# LAN.net
KiCad netlist of a schematic drawn in Altium Designer
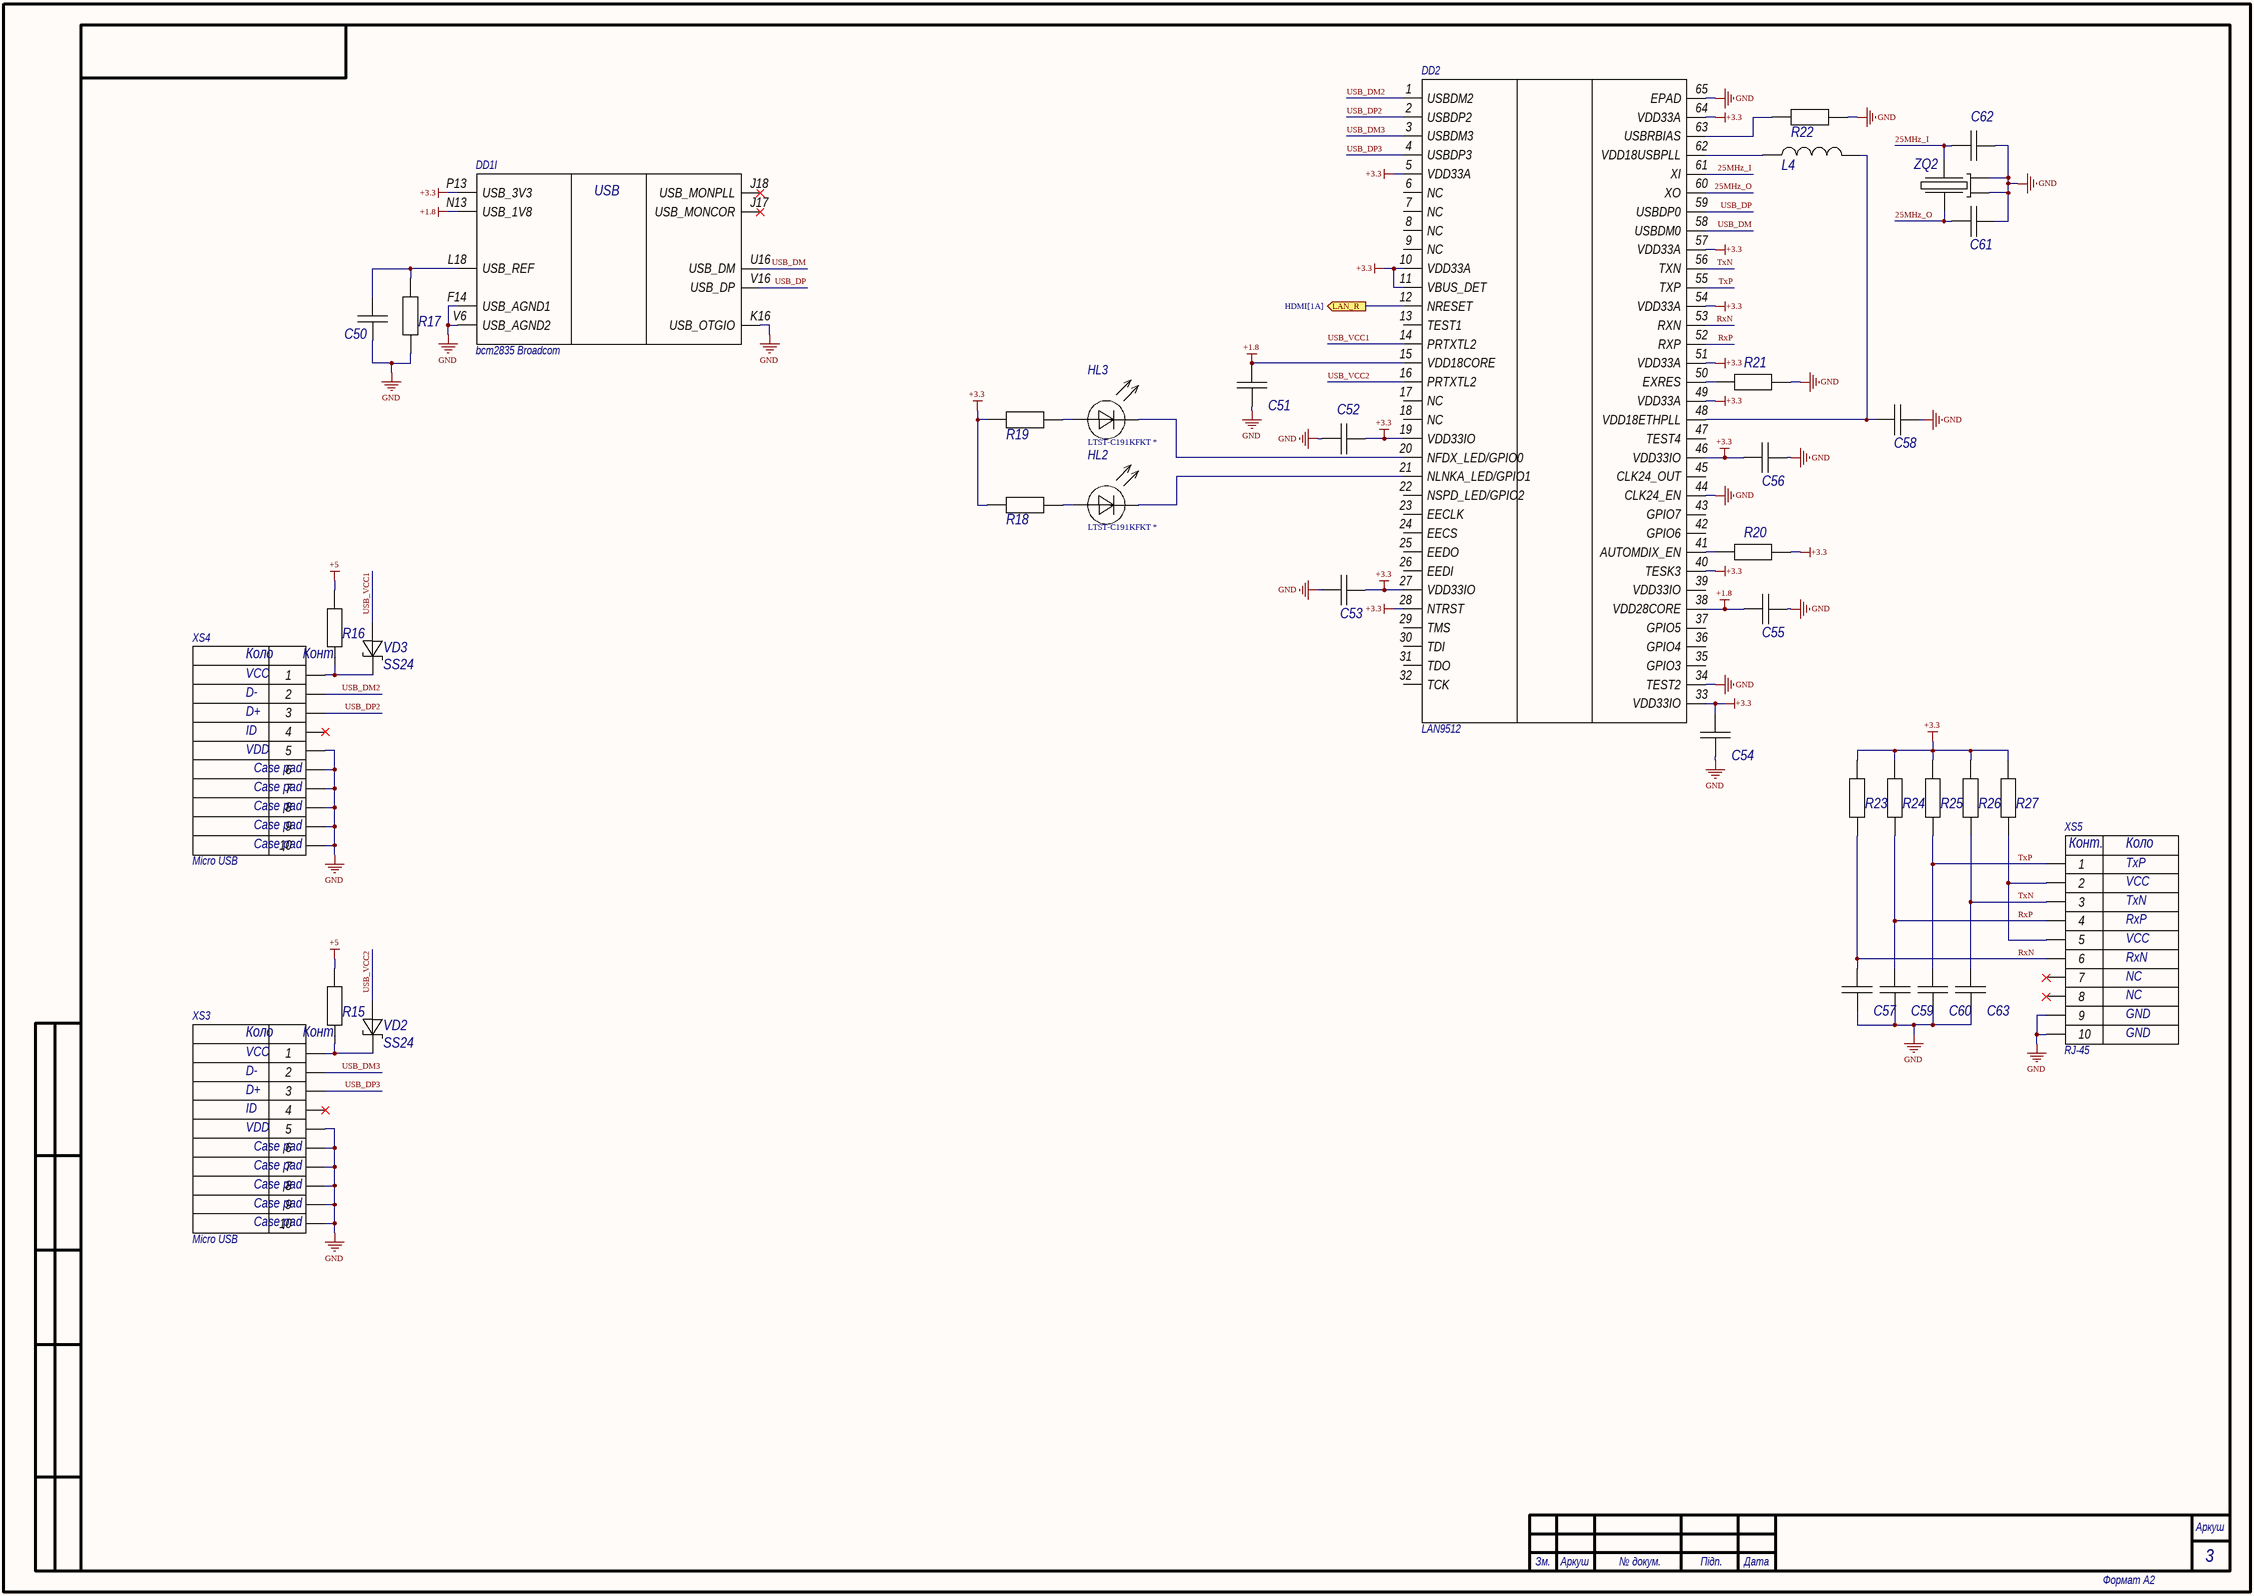
[diagram p0: LAN.SchDoc]

(export (version "E")
  (design (tool "Eeschema 10.0.6"))
  (components
    (comp (ref "C50")
      (value "C-0603 * * * * *")
      (footprint "С-0603")
      (description "Generic")
      (libsource (lib "Schlib1") (part "С-0603"))
    )
    (comp (ref "C51")
      (value "C-0402 * * * * *")
      (footprint "C-0402")
      (description "Generic")
      (libsource (lib "Schlib1") (part "С-0402"))
    )
    (comp (ref "C52")
      (value "C-0402 * * * * *")
      (footprint "C-0402")
      (description "Generic")
      (libsource (lib "Schlib1") (part "С-0402"))
    )
    (comp (ref "C53")
      (value "C-0402 * * * * *")
      (footprint "C-0402")
      (description "Generic")
      (libsource (lib "Schlib1") (part "С-0402"))
    )
    (comp (ref "C54")
      (value "C-0402 * * * * *")
      (footprint "C-0402")
      (description "Generic")
      (libsource (lib "Schlib1") (part "С-0402"))
    )
    (comp (ref "C55")
      (value "C-0402 * * * * *")
      (footprint "C-0402")
      (description "Generic")
      (libsource (lib "Schlib1") (part "С-0402"))
    )
    (comp (ref "C56")
      (value "C-0402 * * * * *")
      (footprint "C-0402")
      (description "Generic")
      (libsource (lib "Schlib1") (part "С-0402"))
    )
    (comp (ref "C57")
      (value "C-0603 * * * * *")
      (footprint "С-0603")
      (description "Generic")
      (libsource (lib "Schlib1") (part "С-0603"))
    )
    (comp (ref "C58")
      (value "C-0402 * * * * *")
      (footprint "C-0402")
      (description "Generic")
      (libsource (lib "Schlib1") (part "С-0402"))
    )
    (comp (ref "C59")
      (value "C-0603 * * * * *")
      (footprint "С-0603")
      (description "Generic")
      (libsource (lib "Schlib1") (part "С-0603"))
    )
    (comp (ref "C60")
      (value "C-0603 * * * * *")
      (footprint "С-0603")
      (description "Generic")
      (libsource (lib "Schlib1") (part "С-0603"))
    )
    (comp (ref "C61")
      (value "C-0402 * * * * *")
      (footprint "C-0402")
      (description "Generic")
      (libsource (lib "Schlib1") (part "С-0402"))
    )
    (comp (ref "C62")
      (value "C-0402 * * * * *")
      (footprint "C-0402")
      (description "Generic")
      (libsource (lib "Schlib1") (part "С-0402"))
    )
    (comp (ref "C63")
      (value "C-0603 * * * * *")
      (footprint "С-0603")
      (description "Generic")
      (libsource (lib "Schlib1") (part "С-0603"))
    )
    (comp (ref "DD1")
      (value "bcm2835 Broadcom")
      (footprint "BGA81C65P18X18_1200X1200")
      (description "BCM2835 ARM-based processor")
      (fields (field (name "MANUFACTURER") "Broadcom"))
      (libsource (lib "Schlib1") (part "bcm2835"))
    )
    (comp (ref "DD2")
      (value "LAN9512")
      (footprint "QFN64_9x9MC_MCH")
      (description "Ethernet + USB Controller")
      (libsource (lib "Schlib1") (part "LAN9512"))
    )
    (comp (ref "HL2")
      (value "LTST-C191KFKT *")
      (footprint "LED_DIALIGHT_598_DIA")
      (description "Generic LED 0603")
      (libsource (lib "Schlib1") (part "LED 0603"))
    )
    (comp (ref "HL3")
      (value "LTST-C191KFKT *")
      (footprint "LED_DIALIGHT_598_DIA")
      (description "Generic LED 0603")
      (libsource (lib "Schlib1") (part "LED 0603"))
    )
    (comp (ref "L4")
      (value "R-0402 * * * *")
      (footprint "FB-0805")
      (description "Generic")
      (libsource (lib "Schlib1") (part "Ferrite Bead 0805"))
    )
    (comp (ref "R15")
      (value "R-0603 * * * *")
      (footprint "R-0603")
      (description "Generic")
      (libsource (lib "") (part "R-0603_1"))
    )
    (comp (ref "R16")
      (value "R-0603 * * * *")
      (footprint "R-0603")
      (description "Generic")
      (libsource (lib "") (part "R-0603_1"))
    )
    (comp (ref "R17")
      (value "R-0603 * * * *")
      (footprint "R-0603")
      (description "Generic")
      (libsource (lib "") (part "R-0603_1"))
    )
    (comp (ref "R18")
      (value "R-0603 * * * *")
      (footprint "R-0603")
      (description "Generic")
      (libsource (lib "Schlib1") (part "R-0603"))
    )
    (comp (ref "R19")
      (value "R-0603 * * * *")
      (footprint "R-0603")
      (description "Generic")
      (libsource (lib "Schlib1") (part "R-0603"))
    )
    (comp (ref "R20")
      (value "R-0402 * * * *")
      (footprint "R-0402")
      (description "Generic")
      (libsource (lib "Schlib1") (part "R-0402"))
    )
    (comp (ref "R21")
      (value "R-0402 * * * *")
      (footprint "R-0402")
      (description "Generic")
      (libsource (lib "Schlib1") (part "R-0402"))
    )
    (comp (ref "R22")
      (value "R-0402 * * * *")
      (footprint "R-0402")
      (description "Generic")
      (libsource (lib "Schlib1") (part "R-0402"))
    )
    (comp (ref "R23")
      (value "R-0603 * * * *")
      (footprint "R-0603")
      (description "Generic")
      (libsource (lib "") (part "R-0603_2"))
    )
    (comp (ref "R24")
      (value "R-0603 * * * *")
      (footprint "R-0603")
      (description "Generic")
      (libsource (lib "") (part "R-0603_2"))
    )
    (comp (ref "R25")
      (value "R-0603 * * * *")
      (footprint "R-0603")
      (description "Generic")
      (libsource (lib "") (part "R-0603_2"))
    )
    (comp (ref "R26")
      (value "R-0603 * * * *")
      (footprint "R-0603")
      (description "Generic")
      (libsource (lib "") (part "R-0603_2"))
    )
    (comp (ref "R27")
      (value "R-0603 * * * *")
      (footprint "R-0603")
      (description "Generic")
      (libsource (lib "") (part "R-0603_2"))
    )
    (comp (ref "VD2")
      (value "SS24 *")
      (footprint "SS14")
      (description "SS24 Shotky")
      (fields (field (name "NAME") "SS24"))
      (libsource (lib "Schlib1") (part "SS24"))
    )
    (comp (ref "VD3")
      (value "SS24 *")
      (footprint "SS14")
      (description "SS24 Shotky")
      (fields (field (name "NAME") "SS24"))
      (libsource (lib "Schlib1") (part "SS24"))
    )
    (comp (ref "XS3")
      (value "Micro USB")
      (footprint "micro-usb")
      (description "Micro-USB connector for SMT mounting")
      (libsource (lib "Schlib1") (part "Micro-USB"))
    )
    (comp (ref "XS4")
      (value "Micro USB")
      (footprint "micro-usb")
      (description "Micro-USB connector for SMT mounting")
      (libsource (lib "Schlib1") (part "Micro-USB"))
    )
    (comp (ref "XS5")
      (value "RJ-45")
      (footprint "CONN8_2041126-1_TEC")
      (description "RJ-45 connector SMT mounting")
      (libsource (lib "Schlib1") (part "RJ-45"))
    )
    (comp (ref "ZQ2")
      (value "TXC19.2 *")
      (footprint "CRYSTAL_TXC_7B")
      (description "TXC19.2 crystal 19.2 MHz")
      (libsource (lib "Schlib1") (part "TXC19.2"))
    )
  )
  (nets
    (net (code "1") (name "+1.8") (class "Default")
      (node (ref "C51") (pin "2") (pinfunction "2_2") (pintype "passive"))
      (node (ref "C55") (pin "2") (pinfunction "2_2") (pintype "passive"))
      (node (ref "DD1") (pin "N13") (pinfunction "USB_1V8_N13") (pintype "passive"))
      (node (ref "DD2") (pin "15") (pinfunction "VDD18CORE_15") (pintype "passive"))
      (node (ref "DD2") (pin "38") (pinfunction "VDD28CORE_38") (pintype "passive"))
    )
    (net (code "2") (name "+3.3") (class "Default")
      (node (ref "C52") (pin "2") (pinfunction "2_2") (pintype "passive"))
      (node (ref "C53") (pin "2") (pinfunction "2_2") (pintype "passive"))
      (node (ref "C54") (pin "2") (pinfunction "2_2") (pintype "passive"))
      (node (ref "C56") (pin "2") (pinfunction "2_2") (pintype "passive"))
      (node (ref "DD1") (pin "P13") (pinfunction "USB_3V3_P13") (pintype "passive"))
      (node (ref "DD2") (pin "10") (pinfunction "VDD33A_10") (pintype "passive"))
      (node (ref "DD2") (pin "11") (pinfunction "VBUS_DET_11") (pintype "passive"))
      (node (ref "DD2") (pin "19") (pinfunction "VDD33IO_19") (pintype "passive"))
      (node (ref "DD2") (pin "27") (pinfunction "VDD33IO_27") (pintype "passive"))
      (node (ref "DD2") (pin "28") (pinfunction "NTRST_28") (pintype "passive"))
      (node (ref "DD2") (pin "33") (pinfunction "VDD33IO_33") (pintype "passive"))
      (node (ref "DD2") (pin "40") (pinfunction "TESK3_40") (pintype "passive"))
      (node (ref "DD2") (pin "46") (pinfunction "VDD33IO_46") (pintype "passive"))
      (node (ref "DD2") (pin "49") (pinfunction "VDD33A_49") (pintype "passive"))
      (node (ref "DD2") (pin "5") (pinfunction "VDD33A_5") (pintype "passive"))
      (node (ref "DD2") (pin "51") (pinfunction "VDD33A_51") (pintype "passive"))
      (node (ref "DD2") (pin "54") (pinfunction "VDD33A_54") (pintype "passive"))
      (node (ref "DD2") (pin "57") (pinfunction "VDD33A_57") (pintype "passive"))
      (node (ref "DD2") (pin "64") (pinfunction "VDD33A_64") (pintype "passive"))
      (node (ref "R18") (pin "1") (pinfunction "1_1") (pintype "passive"))
      (node (ref "R19") (pin "1") (pinfunction "1_1") (pintype "passive"))
      (node (ref "R20") (pin "2") (pinfunction "2_2") (pintype "passive"))
      (node (ref "R23") (pin "1") (pinfunction "1_1") (pintype "passive"))
      (node (ref "R24") (pin "1") (pinfunction "1_1") (pintype "passive"))
      (node (ref "R25") (pin "1") (pinfunction "1_1") (pintype "passive"))
      (node (ref "R26") (pin "1") (pinfunction "1_1") (pintype "passive"))
      (node (ref "R27") (pin "1") (pinfunction "1_1") (pintype "passive"))
    )
    (net (code "3") (name "+5") (class "Default")
      (node (ref "R15") (pin "2") (pinfunction "2_2") (pintype "passive"))
      (node (ref "R16") (pin "2") (pinfunction "2_2") (pintype "passive"))
    )
    (net (code "4") (name "/25MHz_I") (class "Default")
      (node (ref "C62") (pin "1") (pinfunction "1_1") (pintype "passive"))
      (node (ref "DD2") (pin "61") (pinfunction "XI_61") (pintype "passive"))
      (node (ref "ZQ2") (pin "3") (pinfunction "3_3") (pintype "passive"))
    )
    (net (code "5") (name "/25MHz_O") (class "Default")
      (node (ref "C61") (pin "1") (pinfunction "1_1") (pintype "passive"))
      (node (ref "DD2") (pin "60") (pinfunction "XO_60") (pintype "passive"))
      (node (ref "ZQ2") (pin "1") (pinfunction "1_1") (pintype "passive"))
    )
    (net (code "6") (name "/LAN_R") (class "Default")
      (node (ref "DD2") (pin "12") (pinfunction "NRESET_12") (pintype "passive"))
    )
    (net (code "7") (name "/RxN") (class "Default")
      (node (ref "C57") (pin "1") (pinfunction "1_1") (pintype "passive"))
      (node (ref "DD2") (pin "53") (pinfunction "RXN_53") (pintype "passive"))
      (node (ref "R23") (pin "2") (pinfunction "2_2") (pintype "passive"))
      (node (ref "XS5") (pin "6") (pinfunction "6_6") (pintype "passive"))
    )
    (net (code "8") (name "/RxP") (class "Default")
      (node (ref "C59") (pin "1") (pinfunction "1_1") (pintype "passive"))
      (node (ref "DD2") (pin "52") (pinfunction "RXP_52") (pintype "passive"))
      (node (ref "R24") (pin "2") (pinfunction "2_2") (pintype "passive"))
      (node (ref "XS5") (pin "4") (pinfunction "4_4") (pintype "passive"))
    )
    (net (code "9") (name "/TxN") (class "Default")
      (node (ref "C63") (pin "1") (pinfunction "1_1") (pintype "passive"))
      (node (ref "DD2") (pin "56") (pinfunction "TXN_56") (pintype "passive"))
      (node (ref "R26") (pin "2") (pinfunction "2_2") (pintype "passive"))
      (node (ref "XS5") (pin "3") (pinfunction "3_3") (pintype "passive"))
    )
    (net (code "10") (name "/TxP") (class "Default")
      (node (ref "C60") (pin "1") (pinfunction "1_1") (pintype "passive"))
      (node (ref "DD2") (pin "55") (pinfunction "TXP_55") (pintype "passive"))
      (node (ref "R25") (pin "2") (pinfunction "2_2") (pintype "passive"))
      (node (ref "XS5") (pin "1") (pinfunction "1_1") (pintype "passive"))
    )
    (net (code "11") (name "/USB_DM") (class "Default")
      (node (ref "DD1") (pin "U16") (pinfunction "USB_DM_U16") (pintype "passive"))
      (node (ref "DD2") (pin "58") (pinfunction "USBDM0_58") (pintype "passive"))
    )
    (net (code "12") (name "/USB_DM2") (class "Default")
      (node (ref "DD2") (pin "1") (pinfunction "USBDM2_1") (pintype "passive"))
      (node (ref "XS4") (pin "2") (pinfunction "2_2") (pintype "passive"))
    )
    (net (code "13") (name "/USB_DM3") (class "Default")
      (node (ref "DD2") (pin "3") (pinfunction "USBDM3_3") (pintype "passive"))
      (node (ref "XS3") (pin "2") (pinfunction "2_2") (pintype "passive"))
    )
    (net (code "14") (name "/USB_DP") (class "Default")
      (node (ref "DD1") (pin "V16") (pinfunction "USB_DP_V16") (pintype "passive"))
      (node (ref "DD2") (pin "59") (pinfunction "USBDP0_59") (pintype "passive"))
    )
    (net (code "15") (name "/USB_DP2") (class "Default")
      (node (ref "DD2") (pin "2") (pinfunction "USBDP2_2") (pintype "passive"))
      (node (ref "XS4") (pin "3") (pinfunction "3_3") (pintype "passive"))
    )
    (net (code "16") (name "/USB_DP3") (class "Default")
      (node (ref "DD2") (pin "4") (pinfunction "USBDP3_4") (pintype "passive"))
      (node (ref "XS3") (pin "3") (pinfunction "3_3") (pintype "passive"))
    )
    (net (code "17") (name "/USB_VCC1") (class "Default")
      (node (ref "DD2") (pin "14") (pinfunction "PRTXTL2_14") (pintype "passive"))
      (node (ref "VD3") (pin "1") (pinfunction "1_1") (pintype "passive"))
    )
    (net (code "18") (name "/USB_VCC2") (class "Default")
      (node (ref "DD2") (pin "16") (pinfunction "PRTXTL2_16") (pintype "passive"))
      (node (ref "VD2") (pin "1") (pinfunction "1_1") (pintype "passive"))
    )
    (net (code "19") (name "GND") (class "Default")
      (node (ref "C50") (pin "1") (pinfunction "1_1") (pintype "passive"))
      (node (ref "C51") (pin "1") (pinfunction "1_1") (pintype "passive"))
      (node (ref "C52") (pin "1") (pinfunction "1_1") (pintype "passive"))
      (node (ref "C53") (pin "1") (pinfunction "1_1") (pintype "passive"))
      (node (ref "C54") (pin "1") (pinfunction "1_1") (pintype "passive"))
      (node (ref "C55") (pin "1") (pinfunction "1_1") (pintype "passive"))
      (node (ref "C56") (pin "1") (pinfunction "1_1") (pintype "passive"))
      (node (ref "C57") (pin "2") (pinfunction "2_2") (pintype "passive"))
      (node (ref "C58") (pin "1") (pinfunction "1_1") (pintype "passive"))
      (node (ref "C59") (pin "2") (pinfunction "2_2") (pintype "passive"))
      (node (ref "C60") (pin "2") (pinfunction "2_2") (pintype "passive"))
      (node (ref "C61") (pin "2") (pinfunction "2_2") (pintype "passive"))
      (node (ref "C62") (pin "2") (pinfunction "2_2") (pintype "passive"))
      (node (ref "C63") (pin "2") (pinfunction "2_2") (pintype "passive"))
      (node (ref "DD1") (pin "F14") (pinfunction "USB_AGND1_F14") (pintype "passive"))
      (node (ref "DD1") (pin "K16") (pinfunction "USB_OTGIO_K16") (pintype "passive"))
      (node (ref "DD1") (pin "V6") (pinfunction "USB_AGND2_V6") (pintype "passive"))
      (node (ref "DD2") (pin "34") (pinfunction "TEST2_34") (pintype "passive"))
      (node (ref "DD2") (pin "44") (pinfunction "CLK24_EN_44") (pintype "passive"))
      (node (ref "DD2") (pin "65") (pinfunction "EPAD_65") (pintype "passive"))
      (node (ref "R17") (pin "1") (pinfunction "1_1") (pintype "passive"))
      (node (ref "R21") (pin "2") (pinfunction "2_2") (pintype "passive"))
      (node (ref "R22") (pin "2") (pinfunction "2_2") (pintype "passive"))
      (node (ref "XS3") (pin "10") (pinfunction "10_10") (pintype "passive"))
      (node (ref "XS3") (pin "5") (pinfunction "5_5") (pintype "passive"))
      (node (ref "XS3") (pin "6") (pinfunction "6_6") (pintype "passive"))
      (node (ref "XS3") (pin "7") (pinfunction "7_7") (pintype "passive"))
      (node (ref "XS3") (pin "8") (pinfunction "8_8") (pintype "passive"))
      (node (ref "XS3") (pin "9") (pinfunction "9_9") (pintype "passive"))
      (node (ref "XS4") (pin "10") (pinfunction "10_10") (pintype "passive"))
      (node (ref "XS4") (pin "5") (pinfunction "5_5") (pintype "passive"))
      (node (ref "XS4") (pin "6") (pinfunction "6_6") (pintype "passive"))
      (node (ref "XS4") (pin "7") (pinfunction "7_7") (pintype "passive"))
      (node (ref "XS4") (pin "8") (pinfunction "8_8") (pintype "passive"))
      (node (ref "XS4") (pin "9") (pinfunction "9_9") (pintype "passive"))
      (node (ref "XS5") (pin "10") (pinfunction "10_10") (pintype "passive"))
      (node (ref "XS5") (pin "9") (pinfunction "9_9") (pintype "passive"))
      (node (ref "ZQ2") (pin "2") (pinfunction "2_2") (pintype "passive"))
      (node (ref "ZQ2") (pin "4") (pinfunction "4_4") (pintype "passive"))
    )
    (net (code "20") (name "Net-(DD1I-USB_REF)") (class "Default")
      (node (ref "C50") (pin "2") (pinfunction "2_2") (pintype "passive"))
      (node (ref "DD1") (pin "L18") (pinfunction "USB_REF_L18") (pintype "passive"))
      (node (ref "R17") (pin "2") (pinfunction "2_2") (pintype "passive"))
    )
    (net (code "21") (name "Net-(DD2-AUTOMDIX_EN)") (class "Default")
      (node (ref "DD2") (pin "41") (pinfunction "AUTOMDIX_EN_41") (pintype "passive"))
      (node (ref "R20") (pin "1") (pinfunction "1_1") (pintype "passive"))
    )
    (net (code "22") (name "Net-(DD2-EXRES)") (class "Default")
      (node (ref "DD2") (pin "50") (pinfunction "EXRES_50") (pintype "passive"))
      (node (ref "R21") (pin "1") (pinfunction "1_1") (pintype "passive"))
    )
    (net (code "23") (name "Net-(DD2-NFDX_LED{slash}GPIO0)") (class "Default")
      (node (ref "DD2") (pin "20") (pinfunction "NFDX_LED/GPIO0_20") (pintype "passive"))
      (node (ref "HL3") (pin "2") (pinfunction "2_2") (pintype "passive"))
    )
    (net (code "24") (name "Net-(DD2-NLNKA_LED{slash}GPIO1)") (class "Default")
      (node (ref "DD2") (pin "21") (pinfunction "NLNKA_LED/GPIO1_21") (pintype "passive"))
      (node (ref "HL2") (pin "2") (pinfunction "2_2") (pintype "passive"))
    )
    (net (code "25") (name "Net-(DD2-USBRBIAS)") (class "Default")
      (node (ref "DD2") (pin "63") (pinfunction "USBRBIAS_63") (pintype "passive"))
      (node (ref "R22") (pin "1") (pinfunction "1_1") (pintype "passive"))
    )
    (net (code "26") (name "Net-(DD2-VDD18ETHPLL)") (class "Default")
      (node (ref "C58") (pin "2") (pinfunction "2_2") (pintype "passive"))
      (node (ref "DD2") (pin "48") (pinfunction "VDD18ETHPLL_48") (pintype "passive"))
      (node (ref "L4") (pin "2") (pinfunction "2_2") (pintype "passive"))
    )
    (net (code "27") (name "Net-(DD2-VDD18USBPLL)") (class "Default")
      (node (ref "DD2") (pin "62") (pinfunction "VDD18USBPLL_62") (pintype "passive"))
      (node (ref "L4") (pin "1") (pinfunction "1_1") (pintype "passive"))
    )
    (net (code "28") (name "Net-(HL2-Pad1)") (class "Default")
      (node (ref "HL2") (pin "1") (pinfunction "1_1") (pintype "passive"))
      (node (ref "R18") (pin "2") (pinfunction "2_2") (pintype "passive"))
    )
    (net (code "29") (name "Net-(HL3-Pad1)") (class "Default")
      (node (ref "HL3") (pin "1") (pinfunction "1_1") (pintype "passive"))
      (node (ref "R19") (pin "2") (pinfunction "2_2") (pintype "passive"))
    )
    (net (code "30") (name "Net-(R15-Pad1)") (class "Default")
      (node (ref "R15") (pin "1") (pinfunction "1_1") (pintype "passive"))
      (node (ref "VD2") (pin "2") (pinfunction "2_2") (pintype "passive"))
      (node (ref "XS3") (pin "1") (pinfunction "1_1") (pintype "passive"))
    )
    (net (code "31") (name "Net-(R16-Pad1)") (class "Default")
      (node (ref "R16") (pin "1") (pinfunction "1_1") (pintype "passive"))
      (node (ref "VD3") (pin "2") (pinfunction "2_2") (pintype "passive"))
      (node (ref "XS4") (pin "1") (pinfunction "1_1") (pintype "passive"))
    )
    (net (code "32") (name "Net-(R27-Pad2)") (class "Default")
      (node (ref "R27") (pin "2") (pinfunction "2_2") (pintype "passive"))
      (node (ref "XS5") (pin "2") (pinfunction "2_2") (pintype "passive"))
      (node (ref "XS5") (pin "5") (pinfunction "5_5") (pintype "passive"))
    )
    (net (code "33") (name "unconnected-(DD1I-USB_MONCOR-PadJ17)") (class "Default")
      (node (ref "DD1") (pin "J17") (pinfunction "USB_MONCOR_J17") (pintype "passive+no_connect"))
    )
    (net (code "34") (name "unconnected-(DD1I-USB_MONPLL-PadJ18)") (class "Default")
      (node (ref "DD1") (pin "J18") (pinfunction "USB_MONPLL_J18") (pintype "passive+no_connect"))
    )
    (net (code "35") (name "unconnected-(DD2-CLK24_OUT-Pad45)") (class "Default")
      (node (ref "DD2") (pin "45") (pinfunction "CLK24_OUT_45") (pintype "passive"))
    )
    (net (code "36") (name "unconnected-(DD2-EECLK-Pad23)") (class "Default")
      (node (ref "DD2") (pin "23") (pinfunction "EECLK_23") (pintype "passive"))
    )
    (net (code "37") (name "unconnected-(DD2-EECS-Pad24)") (class "Default")
      (node (ref "DD2") (pin "24") (pinfunction "EECS_24") (pintype "passive"))
    )
    (net (code "38") (name "unconnected-(DD2-EEDI-Pad26)") (class "Default")
      (node (ref "DD2") (pin "26") (pinfunction "EEDI_26") (pintype "passive"))
    )
    (net (code "39") (name "unconnected-(DD2-EEDO-Pad25)") (class "Default")
      (node (ref "DD2") (pin "25") (pinfunction "EEDO_25") (pintype "passive"))
    )
    (net (code "40") (name "unconnected-(DD2-GPIO3-Pad35)") (class "Default")
      (node (ref "DD2") (pin "35") (pinfunction "GPIO3_35") (pintype "passive"))
    )
    (net (code "41") (name "unconnected-(DD2-GPIO4-Pad36)") (class "Default")
      (node (ref "DD2") (pin "36") (pinfunction "GPIO4_36") (pintype "passive"))
    )
    (net (code "42") (name "unconnected-(DD2-GPIO5-Pad37)") (class "Default")
      (node (ref "DD2") (pin "37") (pinfunction "GPIO5_37") (pintype "passive"))
    )
    (net (code "43") (name "unconnected-(DD2-GPIO6-Pad42)") (class "Default")
      (node (ref "DD2") (pin "42") (pinfunction "GPIO6_42") (pintype "passive"))
    )
    (net (code "44") (name "unconnected-(DD2-GPIO7-Pad43)") (class "Default")
      (node (ref "DD2") (pin "43") (pinfunction "GPIO7_43") (pintype "passive"))
    )
    (net (code "45") (name "unconnected-(DD2-NC-Pad6)") (class "Default")
      (node (ref "DD2") (pin "6") (pinfunction "NC_6") (pintype "passive"))
    )
    (net (code "46") (name "unconnected-(DD2-NC-Pad7)") (class "Default")
      (node (ref "DD2") (pin "7") (pinfunction "NC_7") (pintype "passive"))
    )
    (net (code "47") (name "unconnected-(DD2-NC-Pad8)") (class "Default")
      (node (ref "DD2") (pin "8") (pinfunction "NC_8") (pintype "passive"))
    )
    (net (code "48") (name "unconnected-(DD2-NC-Pad9)") (class "Default")
      (node (ref "DD2") (pin "9") (pinfunction "NC_9") (pintype "passive"))
    )
    (net (code "49") (name "unconnected-(DD2-NC-Pad17)") (class "Default")
      (node (ref "DD2") (pin "17") (pinfunction "NC_17") (pintype "passive"))
    )
    (net (code "50") (name "unconnected-(DD2-NC-Pad18)") (class "Default")
      (node (ref "DD2") (pin "18") (pinfunction "NC_18") (pintype "passive"))
    )
    (net (code "51") (name "unconnected-(DD2-NSPD_LED{slash}GPIO2-Pad22)") (class "Default")
      (node (ref "DD2") (pin "22") (pinfunction "NSPD_LED/GPIO2_22") (pintype "passive"))
    )
    (net (code "52") (name "unconnected-(DD2-TCK-Pad32)") (class "Default")
      (node (ref "DD2") (pin "32") (pinfunction "TCK_32") (pintype "passive"))
    )
    (net (code "53") (name "unconnected-(DD2-TDI-Pad30)") (class "Default")
      (node (ref "DD2") (pin "30") (pinfunction "TDI_30") (pintype "passive"))
    )
    (net (code "54") (name "unconnected-(DD2-TDO-Pad31)") (class "Default")
      (node (ref "DD2") (pin "31") (pinfunction "TDO_31") (pintype "passive"))
    )
    (net (code "55") (name "unconnected-(DD2-TEST1-Pad13)") (class "Default")
      (node (ref "DD2") (pin "13") (pinfunction "TEST1_13") (pintype "passive"))
    )
    (net (code "56") (name "unconnected-(DD2-TEST4-Pad47)") (class "Default")
      (node (ref "DD2") (pin "47") (pinfunction "TEST4_47") (pintype "passive"))
    )
    (net (code "57") (name "unconnected-(DD2-TMS-Pad29)") (class "Default")
      (node (ref "DD2") (pin "29") (pinfunction "TMS_29") (pintype "passive"))
    )
    (net (code "58") (name "unconnected-(DD2-VDD33IO-Pad39)") (class "Default")
      (node (ref "DD2") (pin "39") (pinfunction "VDD33IO_39") (pintype "passive"))
    )
    (net (code "59") (name "unconnected-(XS3-Pad4)") (class "Default")
      (node (ref "XS3") (pin "4") (pinfunction "4_4") (pintype "passive+no_connect"))
    )
    (net (code "60") (name "unconnected-(XS4-Pad4)") (class "Default")
      (node (ref "XS4") (pin "4") (pinfunction "4_4") (pintype "passive+no_connect"))
    )
    (net (code "61") (name "unconnected-(XS5-Pad7)") (class "Default")
      (node (ref "XS5") (pin "7") (pinfunction "7_7") (pintype "passive+no_connect"))
    )
    (net (code "62") (name "unconnected-(XS5-Pad8)") (class "Default")
      (node (ref "XS5") (pin "8") (pinfunction "8_8") (pintype "passive+no_connect"))
    )
  )
)
